# POWER.net
KiCad netlist of a schematic drawn in Altium Designer
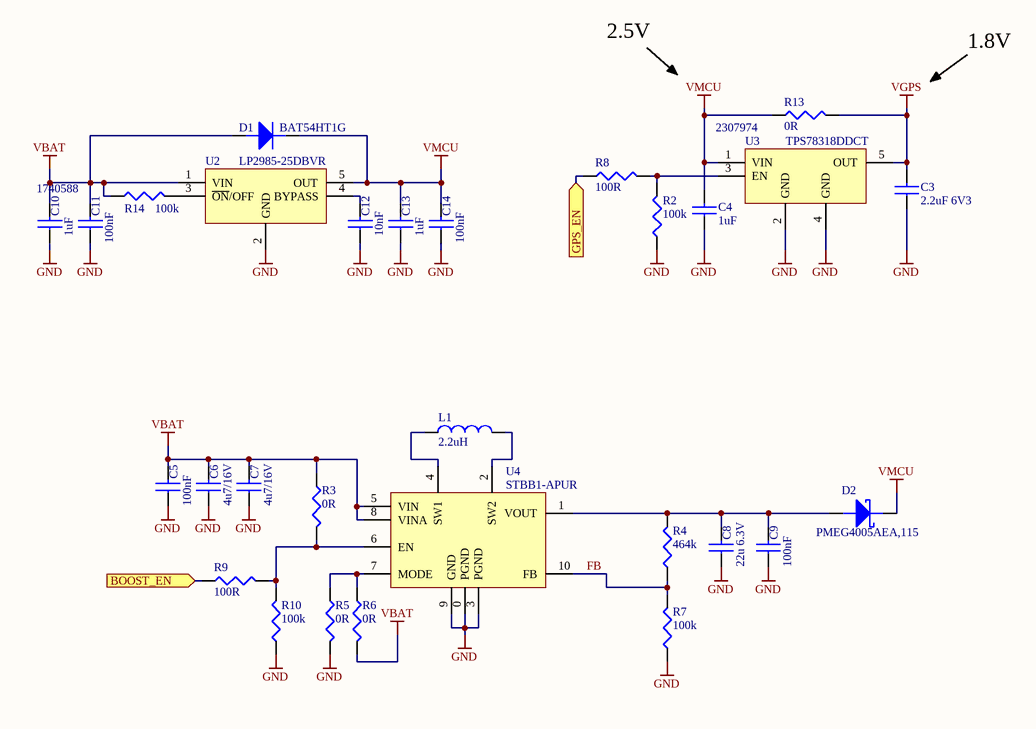
[diagram p0: POWER.SchDoc]

(export (version "E")
  (design (tool "Eeschema 10.0.6"))
  (components
    (comp (ref "C3")
      (value "2.2uF 6V3")
      (footprint "CAP0402")
      (description "CAP CER 2.2UF 6.3V 20% X5R 0402")
      (fields
        (field (name "MANUFACTURER") "Murata")
        (field (name "MANUFACTURER PART NUMBER") "GRM155R60J225ME15D")
      )
      (libsource (lib "Passive") (part "C - 2.2uF/6V3/0402"))
    )
    (comp (ref "C4")
      (value "1uF")
      (footprint "CAP0402")
      (description "CAP CER 1UF 10V 20% X5R 0402")
      (fields
        (field (name "MANUFACTURER") "Murata")
        (field (name "MANUFACTURER PART NUMBER") "GRM155R61A105ME15D")
      )
      (libsource (lib "Passive") (part "C - 1uF/0402"))
    )
    (comp (ref "C5")
      (value "100nF")
      (footprint "CAP0402")
      (fields
        (field (name "MANUFACTURER") "Multicomp")
        (field (name "MANUFACTURER PART NUMBER") "MC0402X104J160CT")
        (field (name "TOLERANCE") "5%")
      )
      (libsource (lib "Passive") (part "C - 100nF/0402"))
    )
    (comp (ref "C6")
      (value "4u7/16V")
      (footprint "CAP0603")
      (description "MURATA - GRM188R61C475KAAJD - CAP, MLCC, X5R, 4.7UF, 16V, 0603")
      (fields
        (field (name "MANUFACTURER") "MURATA")
        (field (name "MANUFACTURER PART NUMBER") "GRM188R61C475KAAJD")
      )
      (libsource (lib "Passive") (part "C - 4u7  16V 0603"))
    )
    (comp (ref "C7")
      (value "4u7/16V")
      (footprint "CAP0603")
      (description "MURATA - GRM188R61C475KAAJD - CAP, MLCC, X5R, 4.7UF, 16V, 0603")
      (fields
        (field (name "MANUFACTURER") "MURATA")
        (field (name "MANUFACTURER PART NUMBER") "GRM188R61C475KAAJD")
      )
      (libsource (lib "Passive") (part "C - 4u7  16V 0603"))
    )
    (comp (ref "C8")
      (value "22u 6.3V")
      (footprint "CAP0805")
      (description "MULTICOMP - MC0805X226M6R3CT - CAP, MLCC, X5R, 22UF, 0805")
      (fields
        (field (name "MANUFACTURER") "MULTICOMP")
        (field (name "MANUFACTURER PART NUMBER") "MC0805X226M6R3CT")
      )
      (libsource (lib "Passive") (part "C - 22u 6.3V 0805"))
    )
    (comp (ref "C9")
      (value "100nF")
      (footprint "CAP0402")
      (fields
        (field (name "MANUFACTURER") "Multicomp")
        (field (name "MANUFACTURER PART NUMBER") "MC0402X104J160CT")
        (field (name "TOLERANCE") "5%")
      )
      (libsource (lib "Passive") (part "C - 100nF/0402"))
    )
    (comp (ref "C10")
      (value "1uF")
      (footprint "CAP0402")
      (description "CAP CER 1UF 10V 20% X5R 0402")
      (fields
        (field (name "MANUFACTURER") "Murata")
        (field (name "MANUFACTURER PART NUMBER") "GRM155R61A105ME15D")
        (field (name "SUPPLIER PART NUMBER 1") "1740588")
      )
      (libsource (lib "Passive") (part "C - 1uF/0402"))
    )
    (comp (ref "C11")
      (value "100nF")
      (footprint "CAP0402")
      (fields
        (field (name "MANUFACTURER") "Multicomp")
        (field (name "MANUFACTURER PART NUMBER") "MC0402X104J160CT")
        (field (name "TOLERANCE") "5%")
      )
      (libsource (lib "Passive") (part "C - 100nF/0402"))
    )
    (comp (ref "C12")
      (value "10nF")
      (footprint "CAP0402")
      (description "CAP CER 10000PF 16V X7R 0402")
      (fields
        (field (name "MANUFACTURER") "Murata")
        (field (name "MANUFACTURER PART NUMBER") "GRM155R71C103KA01D")
      )
      (libsource (lib "Passive") (part "C - 10nF/0402"))
    )
    (comp (ref "C13")
      (value "1uF")
      (footprint "CAP0402")
      (description "CAP CER 1UF 10V 20% X5R 0402")
      (fields
        (field (name "MANUFACTURER") "Murata")
        (field (name "MANUFACTURER PART NUMBER") "GRM155R61A105ME15D")
      )
      (libsource (lib "Passive") (part "C - 1uF/0402"))
    )
    (comp (ref "C14")
      (value "100nF")
      (footprint "CAP0402")
      (fields
        (field (name "MANUFACTURER") "Multicomp")
        (field (name "MANUFACTURER PART NUMBER") "MC0402X104J160CT")
        (field (name "TOLERANCE") "5%")
      )
      (libsource (lib "Passive") (part "C - 100nF/0402"))
    )
    (comp (ref "D1")
      (value "BAT54HT1G")
      (footprint "SOD-323 2L")
      (description "FAIRCHILD SEMICONDUCTOR - BAT54HT1G - DIODE, SCHOTTKY, 30V, SOD-323")
      (fields (field (name "MANUFACTURER") "FAIRCHILD SEMICONDUCTOR"))
      (libsource (lib "Active") (part "DS - BAT54HT1G"))
    )
    (comp (ref "D2")
      (value "PMEG4005AEA,115")
      (footprint "SOD-323 2L")
      (description "Schottky Rectifier, 40 V, 500 mA, Single")
      (fields
        (field (name "MANUFACTURER") "MICRO COMMERCIAL COMPONENTS")
        (field (name "MANUFACTURER PART NUMBER") "SK34A-TP")
      )
      (libsource (lib "Active") (part "DS - PMEG4005AEA,115"))
    )
    (comp (ref "L1")
      (value "2.2uH")
      (footprint "IND2.3X1.7")
      (fields
        (field (name "MANUFACTURER") "Bourns")
        (field (name "MANUFACTURER PART NUMBER") "SRN2009T-2R2M")
        (field (name "IRNAS PART NO.") "/")
      )
      (libsource (lib "Passive") (part "L - 2.2 uH 900mA"))
    )
    (comp (ref "R2")
      (value "100k")
      (footprint "RES0402")
      (description "MULTICOMP   MCWR04X1003FTL   RES, THICK FILM, 100KOHM, 1%, 0.0625W")
      (fields
        (field (name "MANUFACTURER") "Multicomp")
        (field (name "MANUFACTURER PART NUMBER") "MCWR04X1003FTL")
      )
      (libsource (lib "Passive") (part "R - 100k/0402"))
    )
    (comp (ref "R3")
      (value "0R")
      (footprint "RES0402")
      (description "RESISTOR, 0402, 0R, ANTI SULFURATION")
      (fields
        (field (name "MANUFACTURER") "Multicomp")
        (field (name "MANUFACTURER PART NUMBER") "MCMR04X000PTL")
      )
      (libsource (lib "Passive") (part "R - 0R/0402"))
    )
    (comp (ref "R4")
      (value "464k")
      (footprint "RES0402")
      (description "MULTICOMP - MC0063W06031402K - RES, THICK FILM, 402K, 1%, 0.063W, 0603")
      (fields
        (field (name "MANUFACTURER") "MULTICOMP")
        (field (name "MANUFACTURER PART NUMBER") "MC0063W06031402K")
      )
      (libsource (lib "Passive") (part "R - 402k"))
    )
    (comp (ref "R5")
      (value "0R")
      (footprint "RES0402")
      (description "RESISTOR, 0402, 0R, ANTI SULFURATION")
      (fields
        (field (name "MANUFACTURER") "Multicomp")
        (field (name "MANUFACTURER PART NUMBER") "MCMR04X000PTL")
      )
      (libsource (lib "Passive") (part "R - 0R/0402"))
    )
    (comp (ref "R6")
      (value "0R")
      (footprint "RES0402")
      (description "RESISTOR, 0402, 0R, ANTI SULFURATION")
      (fields
        (field (name "MANUFACTURER") "Multicomp")
        (field (name "MANUFACTURER PART NUMBER") "MCMR04X000PTL")
      )
      (libsource (lib "Passive") (part "R - 0R/0402"))
    )
    (comp (ref "R7")
      (value "100k")
      (footprint "RES0402")
      (description "MULTICOMP   MCWR04X1003FTL   RES, THICK FILM, 100KOHM, 1%, 0.0625W")
      (fields
        (field (name "MANUFACTURER") "Multicomp")
        (field (name "MANUFACTURER PART NUMBER") "MCWR04X1003FTL")
      )
      (libsource (lib "Passive") (part "R - 100k/0402"))
    )
    (comp (ref "R8")
      (value "100R")
      (footprint "RES0402")
      (fields
        (field (name "MANUFACTURER") "Multicomp")
        (field (name "MANUFACTURER PART NUMBER") "MCMR04X1000FTL")
        (field (name "TOLERANCE") "1%")
      )
      (libsource (lib "Passive") (part "R - 100R/0402"))
    )
    (comp (ref "R9")
      (value "100R")
      (footprint "RES0402")
      (fields
        (field (name "MANUFACTURER") "Multicomp")
        (field (name "MANUFACTURER PART NUMBER") "MCMR04X1000FTL")
        (field (name "TOLERANCE") "1%")
      )
      (libsource (lib "Passive") (part "R - 100R/0402"))
    )
    (comp (ref "R10")
      (value "100k")
      (footprint "RES0402")
      (description "MULTICOMP   MCWR04X1003FTL   RES, THICK FILM, 100KOHM, 1%, 0.0625W")
      (fields
        (field (name "MANUFACTURER") "Multicomp")
        (field (name "MANUFACTURER PART NUMBER") "MCWR04X1003FTL")
      )
      (libsource (lib "Passive") (part "R - 100k/0402"))
    )
    (comp (ref "R13")
      (value "0R")
      (footprint "RES0402")
      (description "RESISTOR, 0402, 0R, ANTI SULFURATION")
      (fields
        (field (name "MANUFACTURER") "Multicomp")
        (field (name "MANUFACTURER PART NUMBER") "MCMR04X000PTL")
      )
      (libsource (lib "Passive") (part "R - 0R/0402"))
    )
    (comp (ref "R14")
      (value "100k")
      (footprint "RES0402")
      (description "MULTICOMP   MCWR04X1003FTL   RES, THICK FILM, 100KOHM, 1%, 0.0625W")
      (fields
        (field (name "MANUFACTURER") "Multicomp")
        (field (name "MANUFACTURER PART NUMBER") "MCWR04X1003FTL")
      )
      (libsource (lib "Passive") (part "R - 100k/0402"))
    )
    (comp (ref "U2")
      (value "LP2985-25DBVR")
      (footprint "SOT23-5")
      (description "Fixed LDO Voltage Regulator, 2.2V to 16V, 280mV Dropout, 2.5Vout, 150mAout")
      (fields
        (field (name "MANUFACTURER") "ON SEMICONDUCTOR")
        (field (name "MANUFACTURER PART NUMBER") "LM2596DSADJG")
      )
      (libsource (lib "Active") (part "V_LIN - LP2985-25DBVR"))
    )
    (comp (ref "U3")
      (value "TPS78318DDCT")
      (footprint "SOT23-5")
      (description "Fixed LDO Voltage Regulator, 2.2V to 5.5V, 130mV Dropout, 1.8Vout, 150mAout")
      (fields
        (field (name "MANUFACTURER") "ON SEMICONDUCTOR")
        (field (name "MANUFACTURER PART NUMBER") "LM2596DSADJG")
        (field (name "SUPPLIER PART NUMBER 1") "2307974")
      )
      (libsource (lib "Active") (part "V_LIN - TPS78318DDCT"))
    )
    (comp (ref "U4")
      (value "STBB1-APUR")
      (footprint "DFN-10")
      (description "DC-DC Switching Buck-Boost Regulator, Adjustable, 2V-5.5Vin, 1.2V-5.5Vout, 1Aout")
      (fields (field (name "MANUFACTURER") "u-blox") (field (name "MANUFACTURER PART NUMBER") "MAX-M8Q-0"))
      (libsource (lib "Active") (part "V_SW - STBB1-APUR"))
    )
  )
  (nets
    (net (code "1") (name "/BOOST_EN") (class "Default")
      (node (ref "R9") (pin "1") (pinfunction "1_1") (pintype "passive"))
    )
    (net (code "2") (name "/FB") (class "Default")
      (node (ref "R4") (pin "1") (pinfunction "1_1") (pintype "passive"))
      (node (ref "R7") (pin "2") (pinfunction "2_2") (pintype "passive"))
      (node (ref "U4") (pin "10") (pinfunction "FB_10") (pintype "passive"))
    )
    (net (code "3") (name "/GPS_EN") (class "Default")
      (node (ref "R8") (pin "1") (pinfunction "1_1") (pintype "passive"))
    )
    (net (code "4") (name "GND") (class "Default")
      (node (ref "C10") (pin "1") (pinfunction "1_1") (pintype "passive"))
      (node (ref "C11") (pin "1") (pinfunction "1_1") (pintype "passive"))
      (node (ref "C12") (pin "1") (pinfunction "1_1") (pintype "passive"))
      (node (ref "C13") (pin "1") (pinfunction "1_1") (pintype "passive"))
      (node (ref "C14") (pin "1") (pinfunction "1_1") (pintype "passive"))
      (node (ref "C3") (pin "1") (pinfunction "1_1") (pintype "passive"))
      (node (ref "C4") (pin "1") (pinfunction "1_1") (pintype "passive"))
      (node (ref "C5") (pin "1") (pinfunction "1_1") (pintype "passive"))
      (node (ref "C6") (pin "1") (pinfunction "1_1") (pintype "passive"))
      (node (ref "C7") (pin "1") (pinfunction "1_1") (pintype "passive"))
      (node (ref "C8") (pin "1") (pinfunction "1_1") (pintype "passive"))
      (node (ref "C9") (pin "1") (pinfunction "1_1") (pintype "passive"))
      (node (ref "R10") (pin "1") (pinfunction "1_1") (pintype "passive"))
      (node (ref "R2") (pin "1") (pinfunction "1_1") (pintype "passive"))
      (node (ref "R5") (pin "2") (pinfunction "2_2") (pintype "passive"))
      (node (ref "R7") (pin "1") (pinfunction "1_1") (pintype "passive"))
      (node (ref "U2") (pin "2") (pinfunction "GND_2") (pintype "open_collector"))
      (node (ref "U3") (pin "2") (pinfunction "GND_2") (pintype "open_collector"))
      (node (ref "U3") (pin "4") (pinfunction "GND_4") (pintype "open_collector"))
      (node (ref "U4") (pin "0") (pinfunction "PGND_0") (pintype "passive"))
      (node (ref "U4") (pin "3") (pinfunction "PGND_3") (pintype "passive"))
      (node (ref "U4") (pin "9") (pinfunction "GND_9") (pintype "passive"))
    )
    (net (code "5") (name "Net-(D2-ANODE)") (class "Default")
      (node (ref "C8") (pin "2") (pinfunction "2_2") (pintype "passive"))
      (node (ref "C9") (pin "2") (pinfunction "2_2") (pintype "passive"))
      (node (ref "D2") (pin "2") (pinfunction "ANODE_2") (pintype "passive"))
      (node (ref "R4") (pin "2") (pinfunction "2_2") (pintype "passive"))
      (node (ref "U4") (pin "1") (pinfunction "VOUT_1") (pintype "passive"))
    )
    (net (code "6") (name "Net-(U2-BYPASS)") (class "Default")
      (node (ref "C12") (pin "2") (pinfunction "2_2") (pintype "passive"))
      (node (ref "U2") (pin "4") (pinfunction "BYPASS_4") (pintype "open_collector"))
    )
    (net (code "7") (name "Net-(U2-~{ON}{slash}OFF)") (class "Default")
      (node (ref "R14") (pin "2") (pinfunction "2_2") (pintype "passive"))
      (node (ref "U2") (pin "3") (pinfunction "~{ON}/OFF_3") (pintype "open_collector"))
    )
    (net (code "8") (name "Net-(U3-EN)") (class "Default")
      (node (ref "R2") (pin "2") (pinfunction "2_2") (pintype "passive"))
      (node (ref "R8") (pin "2") (pinfunction "2_2") (pintype "passive"))
      (node (ref "U3") (pin "3") (pinfunction "EN_3") (pintype "open_collector"))
    )
    (net (code "9") (name "Net-(U4-EN)") (class "Default")
      (node (ref "R10") (pin "2") (pinfunction "2_2") (pintype "passive"))
      (node (ref "R3") (pin "2") (pinfunction "2_2") (pintype "passive"))
      (node (ref "R9") (pin "2") (pinfunction "2_2") (pintype "passive"))
      (node (ref "U4") (pin "6") (pinfunction "EN_6") (pintype "passive"))
    )
    (net (code "10") (name "Net-(U4-MODE)") (class "Default")
      (node (ref "R5") (pin "1") (pinfunction "1_1") (pintype "passive"))
      (node (ref "R6") (pin "1") (pinfunction "1_1") (pintype "passive"))
      (node (ref "U4") (pin "7") (pinfunction "MODE_7") (pintype "passive"))
    )
    (net (code "11") (name "Net-(U4-SW1)") (class "Default")
      (node (ref "L1") (pin "1") (pinfunction "1_1") (pintype "passive"))
      (node (ref "U4") (pin "4") (pinfunction "SW1_4") (pintype "passive"))
    )
    (net (code "12") (name "Net-(U4-SW2)") (class "Default")
      (node (ref "L1") (pin "2") (pinfunction "2_2") (pintype "passive"))
      (node (ref "U4") (pin "2") (pinfunction "SW2_2") (pintype "passive"))
    )
    (net (code "13") (name "VBAT") (class "Default")
      (node (ref "C10") (pin "2") (pinfunction "2_2") (pintype "passive"))
      (node (ref "C11") (pin "2") (pinfunction "2_2") (pintype "passive"))
      (node (ref "C5") (pin "2") (pinfunction "2_2") (pintype "passive"))
      (node (ref "C6") (pin "2") (pinfunction "2_2") (pintype "passive"))
      (node (ref "C7") (pin "2") (pinfunction "2_2") (pintype "passive"))
      (node (ref "D1") (pin "2") (pinfunction "ANODE_2") (pintype "passive"))
      (node (ref "R14") (pin "1") (pinfunction "1_1") (pintype "passive"))
      (node (ref "R3") (pin "1") (pinfunction "1_1") (pintype "passive"))
      (node (ref "R6") (pin "2") (pinfunction "2_2") (pintype "passive"))
      (node (ref "U2") (pin "1") (pinfunction "VIN_1") (pintype "open_collector"))
      (node (ref "U4") (pin "5") (pinfunction "VIN_5") (pintype "passive"))
      (node (ref "U4") (pin "8") (pinfunction "VINA_8") (pintype "passive"))
    )
    (net (code "14") (name "VGPS") (class "Default")
      (node (ref "C3") (pin "2") (pinfunction "2_2") (pintype "passive"))
      (node (ref "R13") (pin "2") (pinfunction "2_2") (pintype "passive"))
      (node (ref "U3") (pin "5") (pinfunction "OUT_5") (pintype "open_collector"))
    )
    (net (code "15") (name "VMCU") (class "Default")
      (node (ref "C13") (pin "2") (pinfunction "2_2") (pintype "passive"))
      (node (ref "C14") (pin "2") (pinfunction "2_2") (pintype "passive"))
      (node (ref "C4") (pin "2") (pinfunction "2_2") (pintype "passive"))
      (node (ref "D1") (pin "1") (pinfunction "cathode_1") (pintype "passive"))
      (node (ref "D2") (pin "1") (pinfunction "cathode_1") (pintype "passive"))
      (node (ref "R13") (pin "1") (pinfunction "1_1") (pintype "passive"))
      (node (ref "U2") (pin "5") (pinfunction "OUT_5") (pintype "open_collector"))
      (node (ref "U3") (pin "1") (pinfunction "VIN_1") (pintype "open_collector"))
    )
  )
)
